# mcu_module.net
KiCad netlist of a schematic drawn in EAGLE
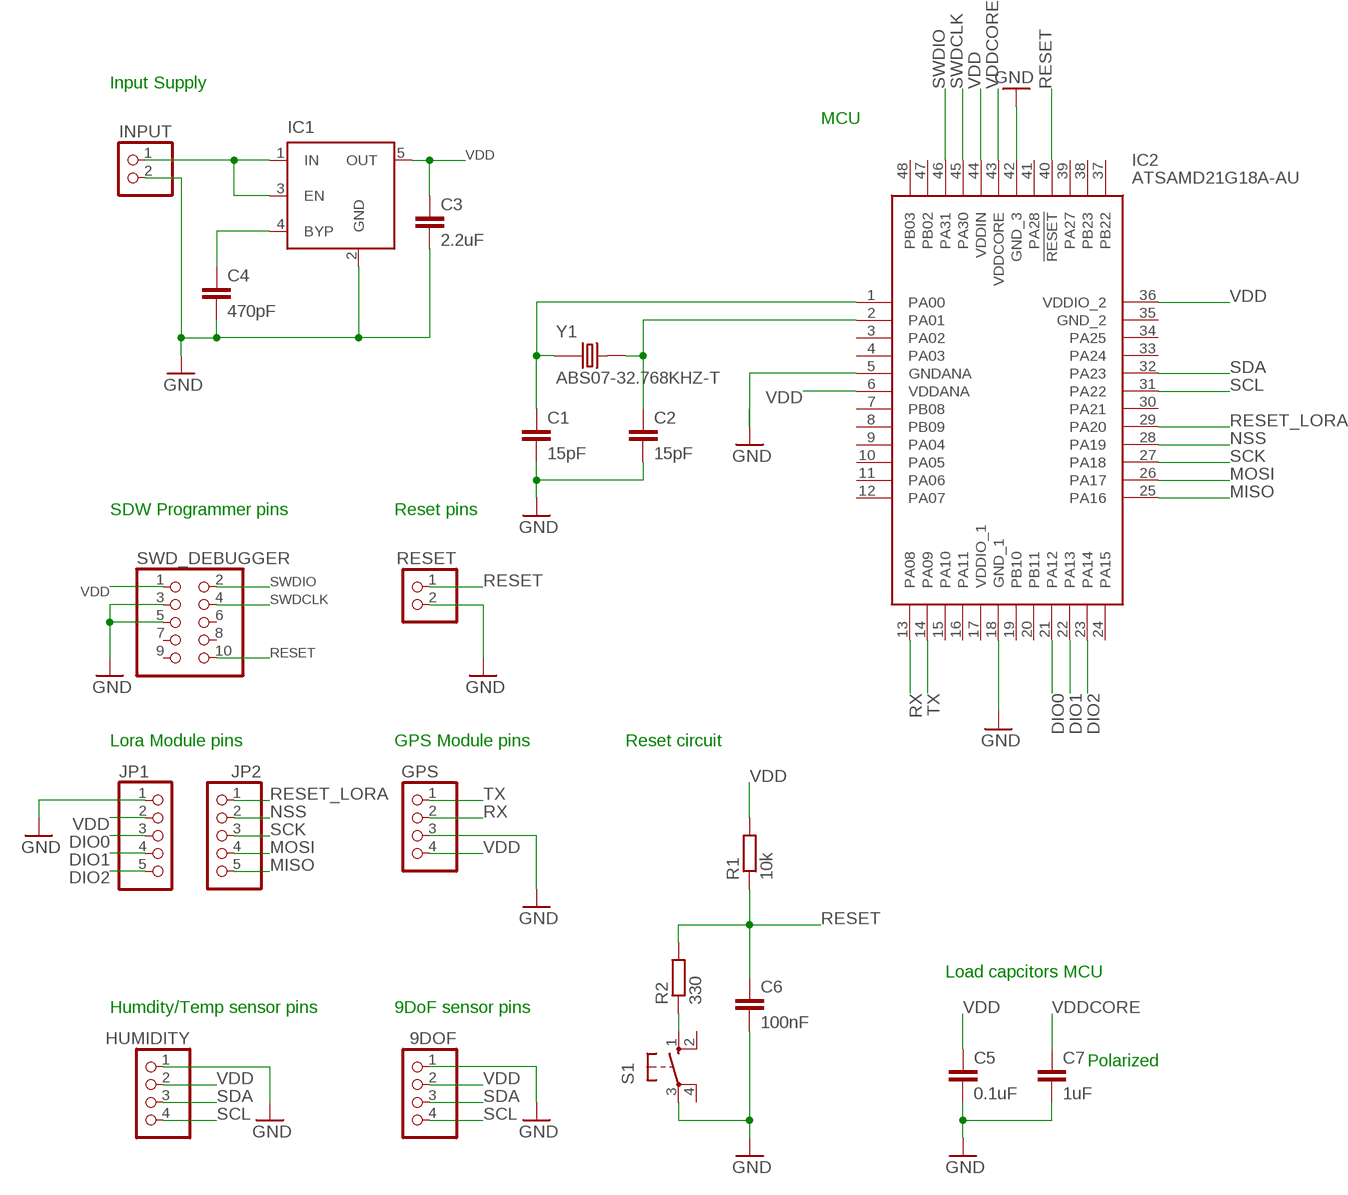
[diagram p0: schematic, sheet 1]

(export (version "E")
  (design (tool "Eeschema 10.0.6"))
  (components
    (comp (ref "9DOF")
      (value "PINHD-1X4")
      (footprint "eagle-import:1X04")
      (libsource (lib "eagle-import") (part "PINHD-1X4"))
    )
    (comp (ref "C1")
      (value "15pF")
      (footprint "eagle-import:C0805")
      (libsource (lib "eagle-import") (part "C-EUC0805"))
    )
    (comp (ref "C2")
      (value "15pF")
      (footprint "eagle-import:C0805")
      (libsource (lib "eagle-import") (part "C-EUC0805"))
    )
    (comp (ref "C3")
      (value "2.2uF")
      (footprint "eagle-import:C0805")
      (libsource (lib "eagle-import") (part "C-EUC0805"))
    )
    (comp (ref "C4")
      (value "470pF")
      (footprint "eagle-import:C0805")
      (libsource (lib "eagle-import") (part "C-EUC0805"))
    )
    (comp (ref "C5")
      (value "0.1uF")
      (footprint "eagle-import:C0805")
      (libsource (lib "eagle-import") (part "C-EUC0805"))
    )
    (comp (ref "C6")
      (value "100nF")
      (footprint "eagle-import:C0805")
      (libsource (lib "eagle-import") (part "C-EUC0805"))
    )
    (comp (ref "C7")
      (value "1uF")
      (footprint "eagle-import:C0805")
      (libsource (lib "eagle-import") (part "C-EUC0805"))
    )
    (comp (ref "GPS")
      (value "PINHD-1X4")
      (footprint "eagle-import:1X04")
      (libsource (lib "eagle-import") (part "PINHD-1X4"))
    )
    (comp (ref "HUMIDITY")
      (value "PINHD-1X4")
      (footprint "eagle-import:1X04")
      (libsource (lib "eagle-import") (part "PINHD-1X4"))
    )
    (comp (ref "IC1")
      (value "MIC5219XX")
      (footprint "eagle-import:SOT23-5")
      (libsource (lib "eagle-import") (part "MIC5219XX"))
    )
    (comp (ref "IC2")
      (value "ATSAMD21G18A-AU")
      (footprint "eagle-import:QFP50P900X900X120-48N")
      (fields
        (field (name "MOUSER_PART_NUMBER") "556-ATSAMD21G18A-AU")
        (field (name "RS_PART_NUMBER") "1773799P")
      )
      (libsource (lib "eagle-import") (part "ATSAMD21G18A-AU"))
    )
    (comp (ref "INPUT")
      (value "PINHD-1X2")
      (footprint "eagle-import:1X02")
      (libsource (lib "eagle-import") (part "PINHD-1X2"))
    )
    (comp (ref "JP1")
      (value "PINHD-1X5")
      (footprint "eagle-import:1X05")
      (libsource (lib "eagle-import") (part "PINHD-1X5"))
    )
    (comp (ref "JP2")
      (value "PINHD-1X5")
      (footprint "eagle-import:1X05")
      (libsource (lib "eagle-import") (part "PINHD-1X5"))
    )
    (comp (ref "R1")
      (value "10k")
      (footprint "eagle-import:R0805")
      (libsource (lib "eagle-import") (part "R-EU_R0805"))
    )
    (comp (ref "R2")
      (value "330")
      (footprint "eagle-import:R0805")
      (libsource (lib "eagle-import") (part "R-EU_R0805"))
    )
    (comp (ref "RESET")
      (value "PINHD-1X2")
      (footprint "eagle-import:1X02")
      (libsource (lib "eagle-import") (part "PINHD-1X2"))
    )
    (comp (ref "S1")
      (value "10-XX")
      (footprint "eagle-import:B3F-10XX")
      (fields (field (name "MPN") "B3F-1000"))
      (libsource (lib "eagle-import") (part "10-XX"))
    )
    (comp (ref "SWD_DEBUGGER")
      (value "PINHD-2X5")
      (footprint "eagle-import:2X05")
      (libsource (lib "eagle-import") (part "PINHD-2X5"))
    )
    (comp (ref "Y1")
      (value "ABS07-32.768KHZ-T")
      (footprint "eagle-import:XTAL_ABS07-32.768KHZ-T")
      (fields (field (name "MF") "Abracon"))
      (libsource (lib "eagle-import") (part "ABS07-32.768KHZ-T"))
    )
  )
  (nets
    (net (code "1") (name "/DIO0") (class "Default")
      (node (ref "IC2") (pin "21") (pinfunction "PA12_21") (pintype "bidirectional"))
      (node (ref "JP1") (pin "3") (pinfunction "3_3") (pintype "passive"))
    )
    (net (code "2") (name "/DIO1") (class "Default")
      (node (ref "IC2") (pin "22") (pinfunction "PA13_22") (pintype "bidirectional"))
      (node (ref "JP1") (pin "4") (pinfunction "4_4") (pintype "passive"))
    )
    (net (code "3") (name "/DIO2") (class "Default")
      (node (ref "IC2") (pin "23") (pinfunction "PA14_23") (pintype "bidirectional"))
      (node (ref "JP1") (pin "5") (pinfunction "5_5") (pintype "passive"))
    )
    (net (code "4") (name "/MISO") (class "Default")
      (node (ref "IC2") (pin "25") (pinfunction "PA16_25") (pintype "bidirectional"))
      (node (ref "JP2") (pin "5") (pinfunction "5_5") (pintype "passive"))
    )
    (net (code "5") (name "/MOSI") (class "Default")
      (node (ref "IC2") (pin "26") (pinfunction "PA17_26") (pintype "bidirectional"))
      (node (ref "JP2") (pin "4") (pinfunction "4_4") (pintype "passive"))
    )
    (net (code "6") (name "/NSS") (class "Default")
      (node (ref "IC2") (pin "28") (pinfunction "PA19_28") (pintype "bidirectional"))
      (node (ref "JP2") (pin "2") (pinfunction "2_2") (pintype "passive"))
    )
    (net (code "7") (name "/RESET") (class "Default")
      (node (ref "C6") (pin "1") (pinfunction "1_1") (pintype "passive"))
      (node (ref "IC2") (pin "40") (pinfunction "~{RESET}_40") (pintype "bidirectional"))
      (node (ref "R1") (pin "1") (pinfunction "1_1") (pintype "passive"))
      (node (ref "R2") (pin "2") (pinfunction "2_2") (pintype "passive"))
      (node (ref "RESET") (pin "1") (pinfunction "1_1") (pintype "passive"))
      (node (ref "SWD_DEBUGGER") (pin "10") (pinfunction "10_10") (pintype "passive"))
    )
    (net (code "8") (name "/RESET_LORA") (class "Default")
      (node (ref "IC2") (pin "29") (pinfunction "PA20_29") (pintype "bidirectional"))
      (node (ref "JP2") (pin "1") (pinfunction "1_1") (pintype "passive"))
    )
    (net (code "9") (name "/RX") (class "Default")
      (node (ref "GPS") (pin "2") (pinfunction "2_2") (pintype "passive"))
      (node (ref "IC2") (pin "13") (pinfunction "PA08_13") (pintype "bidirectional"))
    )
    (net (code "10") (name "/SCK") (class "Default")
      (node (ref "IC2") (pin "27") (pinfunction "PA18_27") (pintype "bidirectional"))
      (node (ref "JP2") (pin "3") (pinfunction "3_3") (pintype "passive"))
    )
    (net (code "11") (name "/SCL") (class "Default")
      (node (ref "9DOF") (pin "4") (pinfunction "4_4") (pintype "passive"))
      (node (ref "HUMIDITY") (pin "4") (pinfunction "4_4") (pintype "passive"))
      (node (ref "IC2") (pin "31") (pinfunction "PA22_31") (pintype "bidirectional"))
    )
    (net (code "12") (name "/SDA") (class "Default")
      (node (ref "9DOF") (pin "3") (pinfunction "3_3") (pintype "passive"))
      (node (ref "HUMIDITY") (pin "3") (pinfunction "3_3") (pintype "passive"))
      (node (ref "IC2") (pin "32") (pinfunction "PA23_32") (pintype "bidirectional"))
    )
    (net (code "13") (name "/SWDCLK") (class "Default")
      (node (ref "IC2") (pin "45") (pinfunction "PA30_45") (pintype "bidirectional"))
      (node (ref "SWD_DEBUGGER") (pin "4") (pinfunction "4_4") (pintype "passive"))
    )
    (net (code "14") (name "/SWDIO") (class "Default")
      (node (ref "IC2") (pin "46") (pinfunction "PA31_46") (pintype "bidirectional"))
      (node (ref "SWD_DEBUGGER") (pin "2") (pinfunction "2_2") (pintype "passive"))
    )
    (net (code "15") (name "/TX") (class "Default")
      (node (ref "GPS") (pin "1") (pinfunction "1_1") (pintype "passive"))
      (node (ref "IC2") (pin "14") (pinfunction "PA09_14") (pintype "bidirectional"))
    )
    (net (code "16") (name "/VDD") (class "Default")
      (node (ref "9DOF") (pin "2") (pinfunction "2_2") (pintype "passive"))
      (node (ref "C3") (pin "1") (pinfunction "1_1") (pintype "passive"))
      (node (ref "C5") (pin "1") (pinfunction "1_1") (pintype "passive"))
      (node (ref "GPS") (pin "4") (pinfunction "4_4") (pintype "passive"))
      (node (ref "HUMIDITY") (pin "2") (pinfunction "2_2") (pintype "passive"))
      (node (ref "IC1") (pin "5") (pinfunction "OUT_5") (pintype "output"))
      (node (ref "IC2") (pin "36") (pinfunction "VDDIO_2_36") (pintype "bidirectional"))
      (node (ref "IC2") (pin "44") (pinfunction "VDDIN_44") (pintype "bidirectional"))
      (node (ref "IC2") (pin "6") (pinfunction "VDDANA_6") (pintype "bidirectional"))
      (node (ref "JP1") (pin "2") (pinfunction "2_2") (pintype "passive"))
      (node (ref "R1") (pin "2") (pinfunction "2_2") (pintype "passive"))
      (node (ref "SWD_DEBUGGER") (pin "1") (pinfunction "1_1") (pintype "passive"))
    )
    (net (code "17") (name "/VDDCORE") (class "Default")
      (node (ref "C7") (pin "1") (pinfunction "1_1") (pintype "passive"))
      (node (ref "IC2") (pin "43") (pinfunction "VDDCORE_43") (pintype "bidirectional"))
    )
    (net (code "18") (name "GND") (class "Default")
      (node (ref "9DOF") (pin "1") (pinfunction "1_1") (pintype "passive"))
      (node (ref "C1") (pin "2") (pinfunction "2_2") (pintype "passive"))
      (node (ref "C2") (pin "2") (pinfunction "2_2") (pintype "passive"))
      (node (ref "C3") (pin "2") (pinfunction "2_2") (pintype "passive"))
      (node (ref "C4") (pin "2") (pinfunction "2_2") (pintype "passive"))
      (node (ref "C5") (pin "2") (pinfunction "2_2") (pintype "passive"))
      (node (ref "C6") (pin "2") (pinfunction "2_2") (pintype "passive"))
      (node (ref "C7") (pin "2") (pinfunction "2_2") (pintype "passive"))
      (node (ref "GPS") (pin "3") (pinfunction "3_3") (pintype "passive"))
      (node (ref "HUMIDITY") (pin "1") (pinfunction "1_1") (pintype "passive"))
      (node (ref "IC1") (pin "2") (pinfunction "GND_2") (pintype "power_in"))
      (node (ref "IC2") (pin "18") (pinfunction "GND_1_18") (pintype "bidirectional"))
      (node (ref "IC2") (pin "42") (pinfunction "GND_3_42") (pintype "bidirectional"))
      (node (ref "IC2") (pin "5") (pinfunction "GNDANA_5") (pintype "bidirectional"))
      (node (ref "INPUT") (pin "2") (pinfunction "2_2") (pintype "passive"))
      (node (ref "JP1") (pin "1") (pinfunction "1_1") (pintype "passive"))
      (node (ref "RESET") (pin "2") (pinfunction "2_2") (pintype "passive"))
      (node (ref "S1") (pin "3") (pinfunction "P_3") (pintype "passive"))
      (node (ref "SWD_DEBUGGER") (pin "3") (pinfunction "3_3") (pintype "passive"))
      (node (ref "SWD_DEBUGGER") (pin "5") (pinfunction "5_5") (pintype "passive"))
    )
    (net (code "19") (name "Net-(IC1-BYP)") (class "Default")
      (node (ref "C4") (pin "1") (pinfunction "1_1") (pintype "passive"))
      (node (ref "IC1") (pin "4") (pinfunction "BYP_4") (pintype "passive"))
    )
    (net (code "20") (name "Net-(IC1-EN)") (class "Default")
      (node (ref "IC1") (pin "1") (pinfunction "IN_1") (pintype "input"))
      (node (ref "IC1") (pin "3") (pinfunction "EN_3") (pintype "input"))
      (node (ref "INPUT") (pin "1") (pinfunction "1_1") (pintype "passive"))
    )
    (net (code "21") (name "Net-(IC2-PA00)") (class "Default")
      (node (ref "C1") (pin "1") (pinfunction "1_1") (pintype "passive"))
      (node (ref "IC2") (pin "1") (pinfunction "PA00_1") (pintype "bidirectional"))
      (node (ref "Y1") (pin "1") (pinfunction "1_1") (pintype "passive"))
    )
    (net (code "22") (name "Net-(IC2-PA01)") (class "Default")
      (node (ref "C2") (pin "1") (pinfunction "1_1") (pintype "passive"))
      (node (ref "IC2") (pin "2") (pinfunction "PA01_2") (pintype "bidirectional"))
      (node (ref "Y1") (pin "2") (pinfunction "2_2") (pintype "passive"))
    )
    (net (code "23") (name "Net-(S1-S)") (class "Default")
      (node (ref "R2") (pin "1") (pinfunction "1_1") (pintype "passive"))
      (node (ref "S1") (pin "1") (pinfunction "S_1") (pintype "passive"))
    )
    (net (code "24") (name "unconnected-(IC2-GND_2-Pad35)") (class "Default")
      (node (ref "IC2") (pin "35") (pinfunction "GND_2_35") (pintype "bidirectional"))
    )
    (net (code "25") (name "unconnected-(IC2-PA02-Pad3)") (class "Default")
      (node (ref "IC2") (pin "3") (pinfunction "PA02_3") (pintype "bidirectional"))
    )
    (net (code "26") (name "unconnected-(IC2-PA03-Pad4)") (class "Default")
      (node (ref "IC2") (pin "4") (pinfunction "PA03_4") (pintype "bidirectional"))
    )
    (net (code "27") (name "unconnected-(IC2-PA04-Pad9)") (class "Default")
      (node (ref "IC2") (pin "9") (pinfunction "PA04_9") (pintype "bidirectional"))
    )
    (net (code "28") (name "unconnected-(IC2-PA05-Pad10)") (class "Default")
      (node (ref "IC2") (pin "10") (pinfunction "PA05_10") (pintype "bidirectional"))
    )
    (net (code "29") (name "unconnected-(IC2-PA06-Pad11)") (class "Default")
      (node (ref "IC2") (pin "11") (pinfunction "PA06_11") (pintype "bidirectional"))
    )
    (net (code "30") (name "unconnected-(IC2-PA07-Pad12)") (class "Default")
      (node (ref "IC2") (pin "12") (pinfunction "PA07_12") (pintype "bidirectional"))
    )
    (net (code "31") (name "unconnected-(IC2-PA10-Pad15)") (class "Default")
      (node (ref "IC2") (pin "15") (pinfunction "PA10_15") (pintype "bidirectional"))
    )
    (net (code "32") (name "unconnected-(IC2-PA11-Pad16)") (class "Default")
      (node (ref "IC2") (pin "16") (pinfunction "PA11_16") (pintype "bidirectional"))
    )
    (net (code "33") (name "unconnected-(IC2-PA15-Pad24)") (class "Default")
      (node (ref "IC2") (pin "24") (pinfunction "PA15_24") (pintype "bidirectional"))
    )
    (net (code "34") (name "unconnected-(IC2-PA21-Pad30)") (class "Default")
      (node (ref "IC2") (pin "30") (pinfunction "PA21_30") (pintype "bidirectional"))
    )
    (net (code "35") (name "unconnected-(IC2-PA24-Pad33)") (class "Default")
      (node (ref "IC2") (pin "33") (pinfunction "PA24_33") (pintype "bidirectional"))
    )
    (net (code "36") (name "unconnected-(IC2-PA25-Pad34)") (class "Default")
      (node (ref "IC2") (pin "34") (pinfunction "PA25_34") (pintype "bidirectional"))
    )
    (net (code "37") (name "unconnected-(IC2-PA27-Pad39)") (class "Default")
      (node (ref "IC2") (pin "39") (pinfunction "PA27_39") (pintype "bidirectional"))
    )
    (net (code "38") (name "unconnected-(IC2-PA28-Pad41)") (class "Default")
      (node (ref "IC2") (pin "41") (pinfunction "PA28_41") (pintype "bidirectional"))
    )
    (net (code "39") (name "unconnected-(IC2-PB02-Pad47)") (class "Default")
      (node (ref "IC2") (pin "47") (pinfunction "PB02_47") (pintype "bidirectional"))
    )
    (net (code "40") (name "unconnected-(IC2-PB03-Pad48)") (class "Default")
      (node (ref "IC2") (pin "48") (pinfunction "PB03_48") (pintype "bidirectional"))
    )
    (net (code "41") (name "unconnected-(IC2-PB08-Pad7)") (class "Default")
      (node (ref "IC2") (pin "7") (pinfunction "PB08_7") (pintype "bidirectional"))
    )
    (net (code "42") (name "unconnected-(IC2-PB09-Pad8)") (class "Default")
      (node (ref "IC2") (pin "8") (pinfunction "PB09_8") (pintype "bidirectional"))
    )
    (net (code "43") (name "unconnected-(IC2-PB10-Pad19)") (class "Default")
      (node (ref "IC2") (pin "19") (pinfunction "PB10_19") (pintype "bidirectional"))
    )
    (net (code "44") (name "unconnected-(IC2-PB11-Pad20)") (class "Default")
      (node (ref "IC2") (pin "20") (pinfunction "PB11_20") (pintype "bidirectional"))
    )
    (net (code "45") (name "unconnected-(IC2-PB22-Pad37)") (class "Default")
      (node (ref "IC2") (pin "37") (pinfunction "PB22_37") (pintype "bidirectional"))
    )
    (net (code "46") (name "unconnected-(IC2-PB23-Pad38)") (class "Default")
      (node (ref "IC2") (pin "38") (pinfunction "PB23_38") (pintype "bidirectional"))
    )
    (net (code "47") (name "unconnected-(IC2-VDDIO_1-Pad17)") (class "Default")
      (node (ref "IC2") (pin "17") (pinfunction "VDDIO_1_17") (pintype "bidirectional"))
    )
    (net (code "48") (name "unconnected-(S1-P1-Pad4)") (class "Default")
      (node (ref "S1") (pin "4") (pinfunction "P1_4") (pintype "passive"))
    )
    (net (code "49") (name "unconnected-(S1-S1-Pad2)") (class "Default")
      (node (ref "S1") (pin "2") (pinfunction "S1_2") (pintype "passive"))
    )
    (net (code "50") (name "unconnected-(SWD_DEBUGGER-Pad6)") (class "Default")
      (node (ref "SWD_DEBUGGER") (pin "6") (pinfunction "6_6") (pintype "passive"))
    )
    (net (code "51") (name "unconnected-(SWD_DEBUGGER-Pad7)") (class "Default")
      (node (ref "SWD_DEBUGGER") (pin "7") (pinfunction "7_7") (pintype "passive"))
    )
    (net (code "52") (name "unconnected-(SWD_DEBUGGER-Pad8)") (class "Default")
      (node (ref "SWD_DEBUGGER") (pin "8") (pinfunction "8_8") (pintype "passive"))
    )
    (net (code "53") (name "unconnected-(SWD_DEBUGGER-Pad9)") (class "Default")
      (node (ref "SWD_DEBUGGER") (pin "9") (pinfunction "9_9") (pintype "passive"))
    )
  )
)
